# Source_and_regulation.net
KiCad netlist of a schematic drawn in Altium Designer
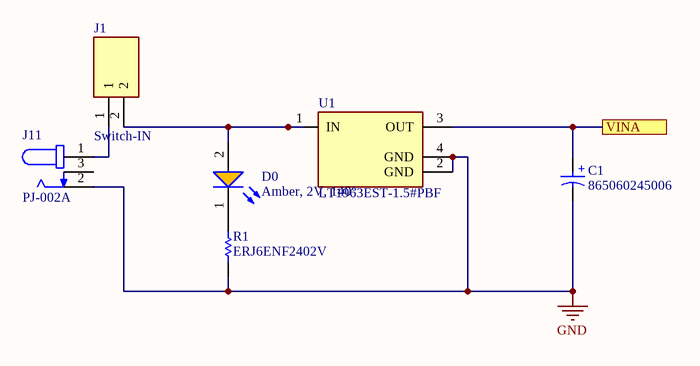
[diagram p0: Source_and_regulation.SchDoc]

(export (version "E")
  (design (tool "Eeschema 10.0.6"))
  (components
    (comp (ref "C1")
      (value "865060245006")
      (footprint "WCAP-ASLL_D6.3H7.7")
      (fields (field (name "TOLERANCE") "20%"))
      (libsource (lib "Altium Content Vault") (part "Capacitor_Polarized"))
    )
    (comp (ref "D0")
      (value "Amber, 2V, 140°")
      (footprint "WL-SMCW_0603_150060xx75000")
      (description "WL-SMCW Mono-color Chip LED Waterclear, SMT, size 0603, Amber, 2V, 140°")
      (fields
        (field (name "MANUFACTURER PART NUMBER") "150060AS75000")
        (field (name "MANUFACTURER") "Wurth Elektronik")
      )
      (libsource (lib "150060AS75000_Altium_WL-SMCW_rev24b") (part "150060AS75000"))
    )
    (comp (ref "J1")
      (value "Switch-IN")
      (footprint "TE_796949-2")
      (description "Connector Terminal Blocks 2 Position 5.08mm Solder Straight Thru-Hole 17.5A/Contact")
      (fields (field (name "MF") "TE Connectivity") (field (name "MP") "796949-2"))
      (libsource (lib "796949-2") (part "796949-2"))
    )
    (comp (ref "J11")
      (value "PJ-002A")
      (footprint "CUI_PJ-002A")
      (description "2.0 x 6.5 mm, 2.5 A, Horizontal, Through Hole, Dc Power Jack Connector")
      (fields (field (name "MF") "CUI Devices"))
      (libsource (lib "PJ-002A") (part "PJ-002A"))
    )
    (comp (ref "R1")
      (value "ERJ6ENF2402V")
      (footprint "RESC2013X70X40ML20T20")
      (fields (field (name "MANUFACTURER") "Panasonic"))
      (libsource (lib "Altium Content Vault") (part "RES"))
    )
    (comp (ref "U1")
      (value "LT1963EST-1.5#PBF")
      (footprint "FP-ST-3-05-08-1630-IPC_C")
      (description "IC REG LINEAR 1.5V 1.5A SOT223-3")
      (libsource (lib "Altium Content Vault") (part "80aa7cff3ef6f61084df0c3a8671dc6"))
    )
  )
  (nets
    (net (code "1") (name "/VINA") (class "Default")
      (node (ref "C1") (pin "1") (pinfunction "P_1") (pintype "passive"))
      (node (ref "U1") (pin "3") (pinfunction "OUT_3") (pintype "passive"))
    )
    (net (code "2") (name "GND") (class "Default")
      (node (ref "C1") (pin "2") (pinfunction "N_2") (pintype "passive"))
      (node (ref "J11") (pin "2") (pinfunction "2_2") (pintype "passive"))
      (node (ref "R1") (pin "1") (pinfunction "1_1") (pintype "passive"))
      (node (ref "U1") (pin "2") (pinfunction "GND_2") (pintype "power_in"))
      (node (ref "U1") (pin "4") (pinfunction "GND_4") (pintype "power_in"))
    )
    (net (code "3") (name "Net-(D0-A)") (class "Default")
      (node (ref "D0") (pin "2") (pinfunction "A_2") (pintype "passive"))
      (node (ref "J1") (pin "2") (pinfunction "2_2") (pintype "passive"))
      (node (ref "U1") (pin "1") (pinfunction "IN_1") (pintype "power_in"))
    )
    (net (code "4") (name "Net-(D0-K)") (class "Default")
      (node (ref "D0") (pin "1") (pinfunction "K_1") (pintype "passive"))
      (node (ref "R1") (pin "2") (pinfunction "2_2") (pintype "passive"))
    )
    (net (code "5") (name "Net-(J1-Pad1)") (class "Default")
      (node (ref "J1") (pin "1") (pinfunction "1_1") (pintype "passive"))
      (node (ref "J11") (pin "1") (pinfunction "1_1") (pintype "passive"))
    )
    (net (code "6") (name "unconnected-(J11-Pad3)") (class "Default")
      (node (ref "J11") (pin "3") (pinfunction "3_3") (pintype "passive"))
    )
  )
)
